# bootloadHID_sch.net
KiCad netlist of a schematic drawn in EAGLE
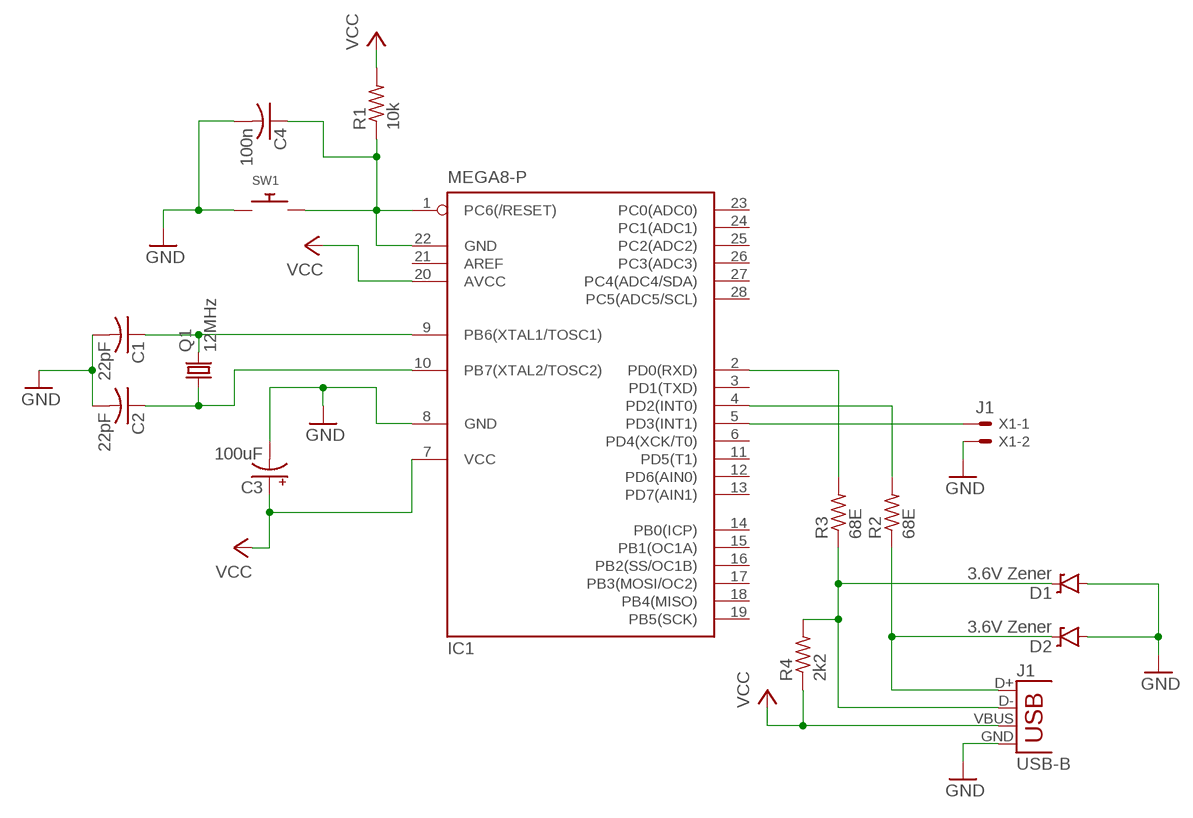
[diagram p0: schematic, sheet 1]

(export (version "E")
  (design (tool "Eeschema 10.0.6"))
  (components
    (comp (ref "C1")
      (value "22pF")
      (footprint "eagle-import:C050-024X044")
      (libsource (lib "eagle-import") (part "C-US050-024X044"))
    )
    (comp (ref "C2")
      (value "22pF")
      (footprint "eagle-import:C050-024X044")
      (libsource (lib "eagle-import") (part "C-US050-024X044"))
    )
    (comp (ref "C3")
      (value "100uF")
      (footprint "eagle-import:E2,5-6")
      (libsource (lib "eagle-import") (part "CPOL-USE2.5-6"))
    )
    (comp (ref "C4")
      (value "100n")
      (footprint "eagle-import:C050-024X044")
      (libsource (lib "eagle-import") (part "C-US050-024X044"))
    )
    (comp (ref "D1")
      (value "3.6V Zener")
      (footprint "eagle-import:DIODE-BZT52")
      (libsource (lib "eagle-import") (part "DIODE-ZENER"))
    )
    (comp (ref "D2")
      (value "3.6V Zener")
      (footprint "eagle-import:DIODE-BZT52")
      (libsource (lib "eagle-import") (part "DIODE-ZENER"))
    )
    (comp (ref "IC1")
      (value "MEGA8-P")
      (footprint "eagle-import:DIL28-3")
      (libsource (lib "eagle-import") (part "MEGA8-P"))
    )
    (comp (ref "J1")
      (value "USB-B")
      (footprint "eagle-import:USB-B-PTH")
      (libsource (lib "eagle-import") (part "USBPTH"))
    )
    (comp (ref "Q1")
      (value "12MHz")
      (footprint "eagle-import:HC49_S")
      (libsource (lib "eagle-import") (part "CRYSTALHC49S"))
    )
    (comp (ref "R1")
      (value "10k")
      (footprint "eagle-import:0204_7")
      (libsource (lib "eagle-import") (part "R-US_0204/7"))
    )
    (comp (ref "R2")
      (value "68E")
      (footprint "eagle-import:0204_7")
      (libsource (lib "eagle-import") (part "R-US_0204/7"))
    )
    (comp (ref "R3")
      (value "68E")
      (footprint "eagle-import:0204_7")
      (libsource (lib "eagle-import") (part "R-US_0204/7"))
    )
    (comp (ref "R4")
      (value "2k2")
      (footprint "eagle-import:0204_7")
      (libsource (lib "eagle-import") (part "R-US_0204/7"))
    )
    (comp (ref "SW1")
      (value "SWITCH_PUSHBUTTONEVQ-PE")
      (footprint "eagle-import:TACT_PANA-EVQ")
      (libsource (lib "eagle-import") (part "SWITCH_PUSHBUTTONEVQ-PE"))
    )
    (comp (ref "X1")
      (value "J1")
      (footprint "eagle-import:22-23-2021")
      (fields (field (name "MF") "MOLEX") (field (name "MPN") "22-23-2021"))
      (libsource (lib "eagle-import") (part "22-23-2021"))
    )
  )
  (nets
    (net (code "1") (name "GND") (class "Default")
      (node (ref "C1") (pin "2") (pinfunction "2_2") (pintype "passive"))
      (node (ref "C2") (pin "2") (pinfunction "2_2") (pintype "passive"))
      (node (ref "C3") (pin "-") (pinfunction "-_-") (pintype "passive"))
      (node (ref "C4") (pin "2") (pinfunction "2_2") (pintype "passive"))
      (node (ref "D1") (pin "A") (pinfunction "A_A") (pintype "passive"))
      (node (ref "D2") (pin "A") (pinfunction "A_A") (pintype "passive"))
      (node (ref "IC1") (pin "8") (pinfunction "GND_8") (pintype "power_in"))
      (node (ref "J1") (pin "GND") (pinfunction "GND_GND") (pintype "bidirectional"))
      (node (ref "SW1") (pin "P$1") (pinfunction "P$1_P$1") (pintype "passive"))
      (node (ref "X1") (pin "2") (pinfunction "S_2") (pintype "passive"))
    )
    (net (code "2") (name "Net-(D1-PadC)") (class "Default")
      (node (ref "D1") (pin "C") (pinfunction "C_C") (pintype "passive"))
      (node (ref "J1") (pin "D-") (pinfunction "D-_D-") (pintype "bidirectional"))
      (node (ref "R3") (pin "1") (pinfunction "1_1") (pintype "passive"))
      (node (ref "R4") (pin "2") (pinfunction "2_2") (pintype "passive"))
    )
    (net (code "3") (name "Net-(D2-PadC)") (class "Default")
      (node (ref "D2") (pin "C") (pinfunction "C_C") (pintype "passive"))
      (node (ref "J1") (pin "D+") (pinfunction "D+_D+") (pintype "bidirectional"))
      (node (ref "R2") (pin "1") (pinfunction "1_1") (pintype "passive"))
    )
    (net (code "4") (name "Net-(IC1-PB6(XTAL1{slash}TOSC1))") (class "Default")
      (node (ref "C1") (pin "1") (pinfunction "1_1") (pintype "passive"))
      (node (ref "IC1") (pin "9") (pinfunction "PB6(XTAL1/TOSC1)_9") (pintype "bidirectional"))
      (node (ref "Q1") (pin "2") (pinfunction "2_2") (pintype "passive"))
    )
    (net (code "5") (name "Net-(IC1-PB7(XTAL2{slash}TOSC2))") (class "Default")
      (node (ref "C2") (pin "1") (pinfunction "1_1") (pintype "passive"))
      (node (ref "IC1") (pin "10") (pinfunction "PB7(XTAL2/TOSC2)_10") (pintype "bidirectional"))
      (node (ref "Q1") (pin "1") (pinfunction "1_1") (pintype "passive"))
    )
    (net (code "6") (name "Net-(IC1-PC6({slash}RESET))") (class "Default")
      (node (ref "C4") (pin "1") (pinfunction "1_1") (pintype "passive"))
      (node (ref "IC1") (pin "1") (pinfunction "PC6(/RESET)_1") (pintype "bidirectional"))
      (node (ref "IC1") (pin "22") (pinfunction "GND_22") (pintype "power_in"))
      (node (ref "R1") (pin "1") (pinfunction "1_1") (pintype "passive"))
      (node (ref "SW1") (pin "P$2") (pinfunction "P$2_P$2") (pintype "passive"))
    )
    (net (code "7") (name "Net-(IC1-PD0(RXD))") (class "Default")
      (node (ref "IC1") (pin "2") (pinfunction "PD0(RXD)_2") (pintype "bidirectional"))
      (node (ref "R3") (pin "2") (pinfunction "2_2") (pintype "passive"))
    )
    (net (code "8") (name "Net-(IC1-PD2(INT0))") (class "Default")
      (node (ref "IC1") (pin "4") (pinfunction "PD2(INT0)_4") (pintype "bidirectional"))
      (node (ref "R2") (pin "2") (pinfunction "2_2") (pintype "passive"))
    )
    (net (code "9") (name "Net-(IC1-PD3(INT1))") (class "Default")
      (node (ref "IC1") (pin "5") (pinfunction "PD3(INT1)_5") (pintype "bidirectional"))
      (node (ref "X1") (pin "1") (pinfunction "S_1") (pintype "passive"))
    )
    (net (code "10") (name "VCC") (class "Default")
      (node (ref "C3") (pin "+") (pinfunction "+_+") (pintype "passive"))
      (node (ref "IC1") (pin "20") (pinfunction "AVCC_20") (pintype "power_in"))
      (node (ref "IC1") (pin "7") (pinfunction "VCC_7") (pintype "power_in"))
      (node (ref "J1") (pin "VBUS") (pinfunction "VBUS_VBUS") (pintype "bidirectional"))
      (node (ref "R1") (pin "2") (pinfunction "2_2") (pintype "passive"))
      (node (ref "R4") (pin "1") (pinfunction "1_1") (pintype "passive"))
    )
    (net (code "11") (name "unconnected-(IC1-AREF-Pad21)") (class "Default")
      (node (ref "IC1") (pin "21") (pinfunction "AREF_21") (pintype "passive"))
    )
    (net (code "12") (name "unconnected-(IC1-PB0(ICP)-Pad14)") (class "Default")
      (node (ref "IC1") (pin "14") (pinfunction "PB0(ICP)_14") (pintype "bidirectional"))
    )
    (net (code "13") (name "unconnected-(IC1-PB1(OC1A)-Pad15)") (class "Default")
      (node (ref "IC1") (pin "15") (pinfunction "PB1(OC1A)_15") (pintype "bidirectional"))
    )
    (net (code "14") (name "unconnected-(IC1-PB2(SS{slash}OC1B)-Pad16)") (class "Default")
      (node (ref "IC1") (pin "16") (pinfunction "PB2(SS/OC1B)_16") (pintype "bidirectional"))
    )
    (net (code "15") (name "unconnected-(IC1-PB3(MOSI{slash}OC2)-Pad17)") (class "Default")
      (node (ref "IC1") (pin "17") (pinfunction "PB3(MOSI/OC2)_17") (pintype "bidirectional"))
    )
    (net (code "16") (name "unconnected-(IC1-PB4(MISO)-Pad18)") (class "Default")
      (node (ref "IC1") (pin "18") (pinfunction "PB4(MISO)_18") (pintype "bidirectional"))
    )
    (net (code "17") (name "unconnected-(IC1-PB5(SCK)-Pad19)") (class "Default")
      (node (ref "IC1") (pin "19") (pinfunction "PB5(SCK)_19") (pintype "bidirectional"))
    )
    (net (code "18") (name "unconnected-(IC1-PC0(ADC0)-Pad23)") (class "Default")
      (node (ref "IC1") (pin "23") (pinfunction "PC0(ADC0)_23") (pintype "bidirectional"))
    )
    (net (code "19") (name "unconnected-(IC1-PC1(ADC1)-Pad24)") (class "Default")
      (node (ref "IC1") (pin "24") (pinfunction "PC1(ADC1)_24") (pintype "bidirectional"))
    )
    (net (code "20") (name "unconnected-(IC1-PC2(ADC2)-Pad25)") (class "Default")
      (node (ref "IC1") (pin "25") (pinfunction "PC2(ADC2)_25") (pintype "bidirectional"))
    )
    (net (code "21") (name "unconnected-(IC1-PC3(ADC3)-Pad26)") (class "Default")
      (node (ref "IC1") (pin "26") (pinfunction "PC3(ADC3)_26") (pintype "bidirectional"))
    )
    (net (code "22") (name "unconnected-(IC1-PC4(ADC4{slash}SDA)-Pad27)") (class "Default")
      (node (ref "IC1") (pin "27") (pinfunction "PC4(ADC4/SDA)_27") (pintype "bidirectional"))
    )
    (net (code "23") (name "unconnected-(IC1-PC5(ADC5{slash}SCL)-Pad28)") (class "Default")
      (node (ref "IC1") (pin "28") (pinfunction "PC5(ADC5/SCL)_28") (pintype "bidirectional"))
    )
    (net (code "24") (name "unconnected-(IC1-PD1(TXD)-Pad3)") (class "Default")
      (node (ref "IC1") (pin "3") (pinfunction "PD1(TXD)_3") (pintype "bidirectional"))
    )
    (net (code "25") (name "unconnected-(IC1-PD4(XCK{slash}T0)-Pad6)") (class "Default")
      (node (ref "IC1") (pin "6") (pinfunction "PD4(XCK/T0)_6") (pintype "bidirectional"))
    )
    (net (code "26") (name "unconnected-(IC1-PD5(T1)-Pad11)") (class "Default")
      (node (ref "IC1") (pin "11") (pinfunction "PD5(T1)_11") (pintype "bidirectional"))
    )
    (net (code "27") (name "unconnected-(IC1-PD6(AIN0)-Pad12)") (class "Default")
      (node (ref "IC1") (pin "12") (pinfunction "PD6(AIN0)_12") (pintype "bidirectional"))
    )
    (net (code "28") (name "unconnected-(IC1-PD7(AIN1)-Pad13)") (class "Default")
      (node (ref "IC1") (pin "13") (pinfunction "PD7(AIN1)_13") (pintype "bidirectional"))
    )
  )
)
